# NodeMCU-Gateway.net
KiCad netlist of a schematic drawn in EAGLE
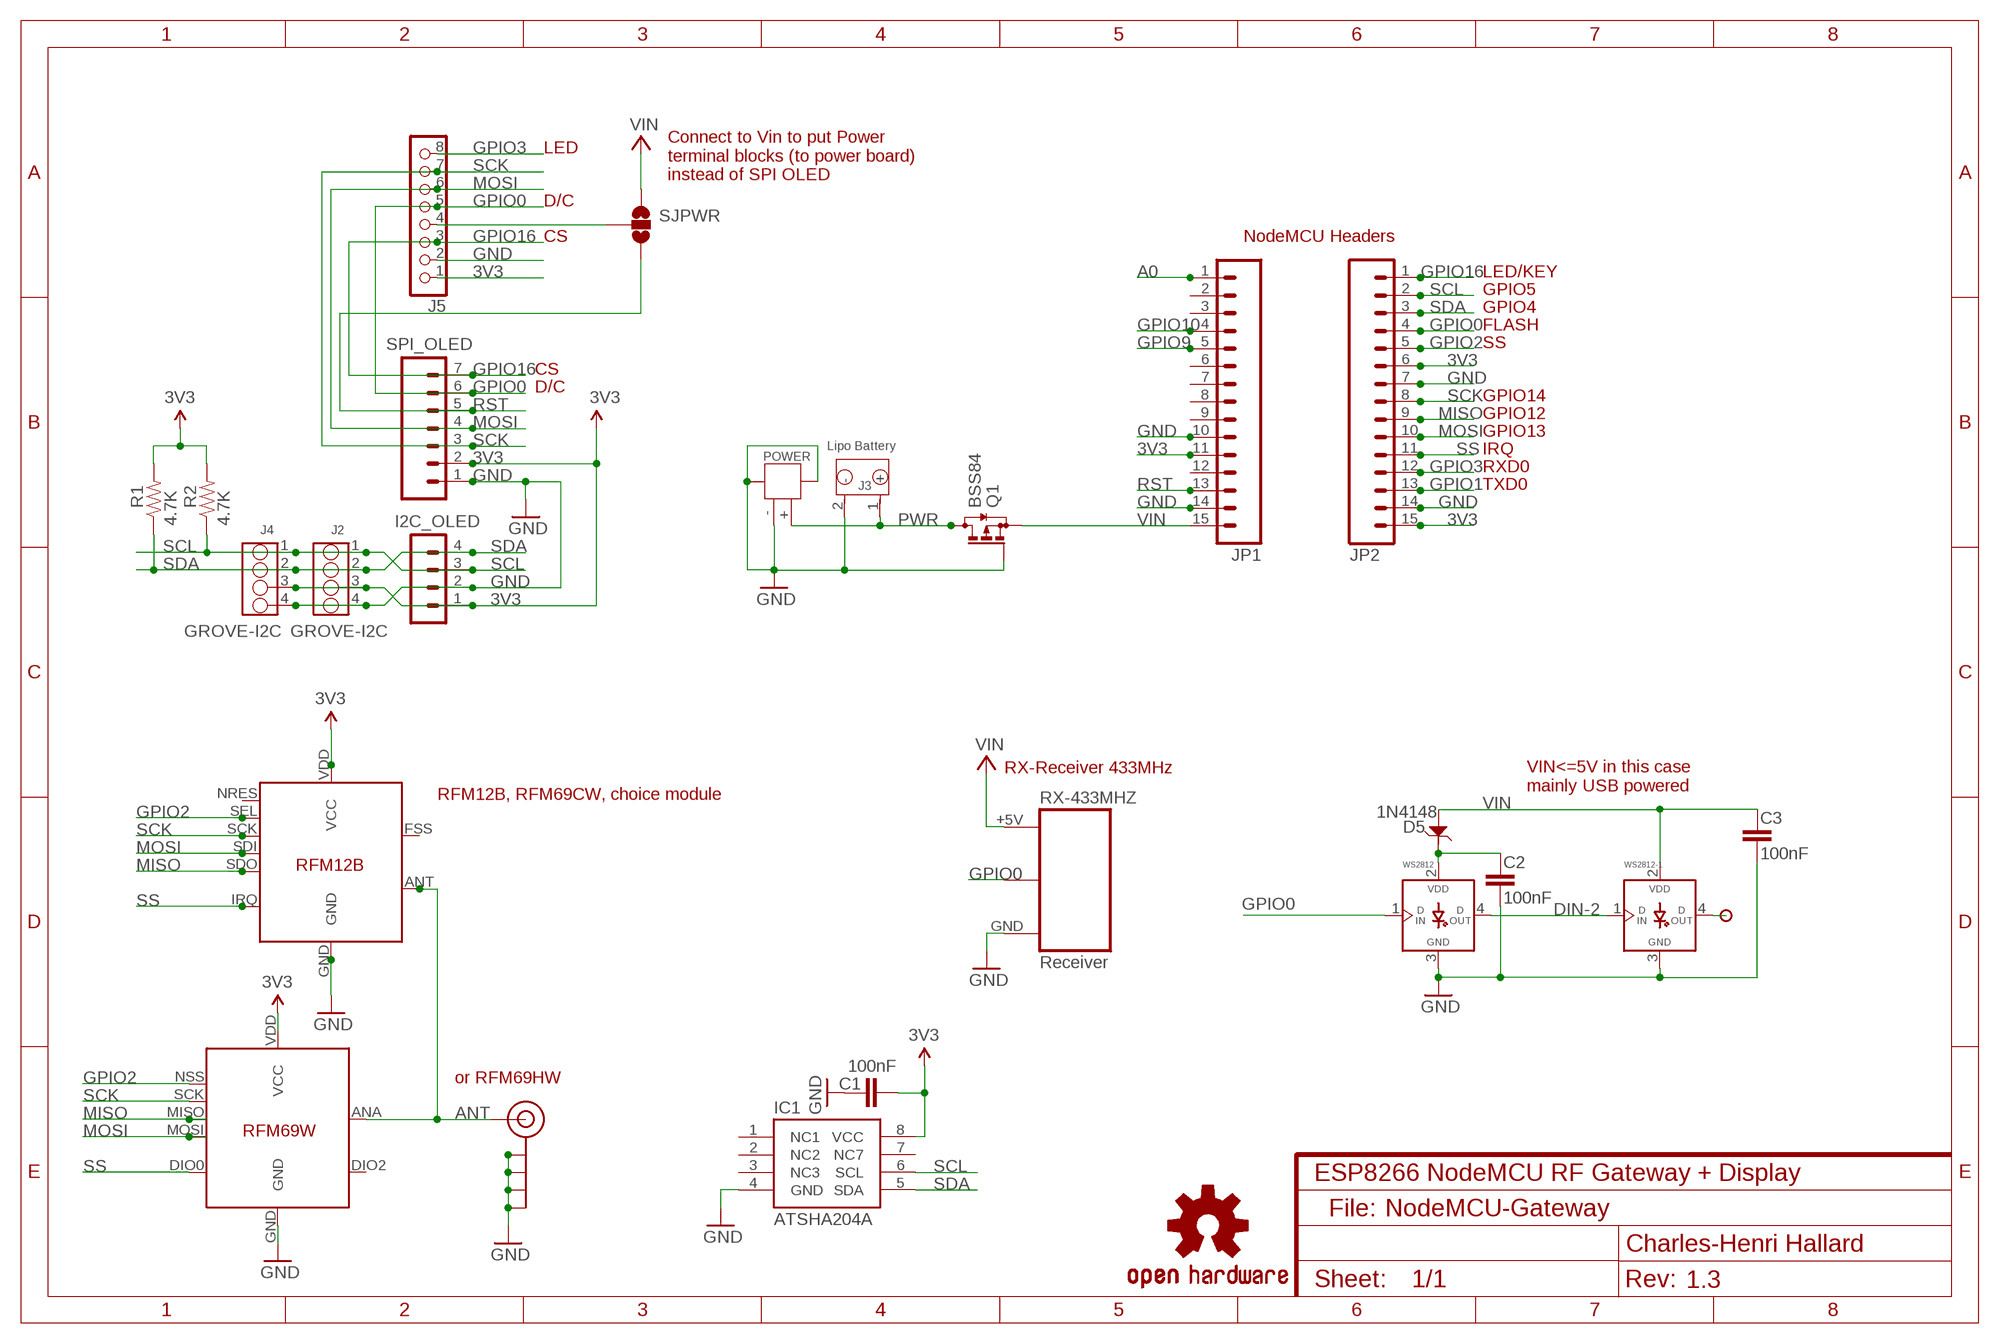
[diagram p0: schematic, sheet 1]

(export (version "E")
  (design (tool "Eeschema 10.0.6"))
  (components
    (comp (ref "C1")
      (value "100nF")
      (footprint "eagle-import:0805-CAP")
      (libsource (lib "eagle-import") (part "CAP0805-CAP"))
    )
    (comp (ref "C2")
      (value "100nF")
      (footprint "eagle-import:0805-CAP")
      (libsource (lib "eagle-import") (part "CAP0805-CAP"))
    )
    (comp (ref "C3")
      (value "100nF")
      (footprint "eagle-import:0805-CAP")
      (libsource (lib "eagle-import") (part "CAP0805-CAP"))
    )
    (comp (ref "D5")
      (value "1N4148")
      (footprint "eagle-import:SOD123-2.7X1.6")
      (libsource (lib "eagle-import") (part "D-ESD-2P-CESD5V0D1"))
    )
    (comp (ref "I2C_OLED")
      (value "CON_HEADER_1X04'LOCK'")
      (footprint "eagle-import:1X04_LOCK")
      (libsource (lib "eagle-import") (part "CON_HEADER_1X04'LOCK'"))
    )
    (comp (ref "IC1")
      (value "ATSHA204A")
      (footprint "eagle-import:SOIC8")
      (libsource (lib "eagle-import") (part "ATSHA204_SOIC8"))
    )
    (comp (ref "J$2")
      (value "ANTENNATINY")
      (footprint "eagle-import:SMA_UFL_PAD_TINY")
      (libsource (lib "eagle-import") (part "ANTENNATINY"))
    )
    (comp (ref "J2")
      (value "GROVE-I2C")
      (footprint "eagle-import:4P-2.0-90D")
      (libsource (lib "eagle-import") (part "GROVE-4P-2.0-3470140P1"))
    )
    (comp (ref "J3")
      (value "Lipo Battery")
      (footprint "eagle-import:2P-2.0-90D")
      (libsource (lib "eagle-import") (part "JST-2P-PW-3410070P1"))
    )
    (comp (ref "J4")
      (value "GROVE-I2C")
      (footprint "eagle-import:4P-2.0")
      (libsource (lib "eagle-import") (part "GROVE-4P-2.0-3470130P1"))
    )
    (comp (ref "J5")
      (value "CON_HEADER_1X08-PTH")
      (footprint "eagle-import:M1X8")
      (libsource (lib "eagle-import") (part "CON_HEADER_1X08-PTH"))
    )
    (comp (ref "JP1")
      (value "M15LOCK")
      (footprint "eagle-import:1X15_LOCK")
      (libsource (lib "eagle-import") (part "M15LOCK"))
    )
    (comp (ref "JP2")
      (value "M15LOCK")
      (footprint "eagle-import:1X15_LOCK")
      (libsource (lib "eagle-import") (part "M15LOCK"))
    )
    (comp (ref "LOGO2")
      (value "OSHW-LOGOL")
      (footprint "eagle-import:OSHW-LOGO-L")
      (libsource (lib "eagle-import") (part "OSHW-LOGOL"))
    )
    (comp (ref "P2")
      (value "PADNORMAL")
      (footprint "eagle-import:PAD")
      (libsource (lib "eagle-import") (part "PADNORMAL"))
    )
    (comp (ref "POWER")
      (value "JST-2P-SMD'2.0'")
      (footprint "eagle-import:2P-SMD-2.0-90D")
      (libsource (lib "eagle-import") (part "JST-2P-SMD'2.0'"))
    )
    (comp (ref "Q1")
      (value "BSS84")
      (footprint "eagle-import:SOT23")
      (libsource (lib "eagle-import") (part "BSS84"))
    )
    (comp (ref "R1")
      (value "4.7K")
      (footprint "eagle-import:0805-RES")
      (libsource (lib "eagle-import") (part "RESISTOR0805-RES"))
    )
    (comp (ref "R2")
      (value "4.7K")
      (footprint "eagle-import:0805-RES")
      (libsource (lib "eagle-import") (part "RESISTOR0805-RES"))
    )
    (comp (ref "RX-433MHZ")
      (value "Receiver")
      (footprint "eagle-import:RF-LINK_RX_NO_SILK")
      (libsource (lib "eagle-import") (part "RF-LINK_RX"))
    )
    (comp (ref "SJPWR")
      (value "JUMPER-PAD-3-2OF3_NC_BY_TRACE_LARGE")
      (footprint "eagle-import:PAD-JUMPER-3-2OF3_NC_BY_TRACE_YES_SILK_LARGE")
      (libsource (lib "eagle-import") (part "JUMPER-PAD-3-2OF3_NC_BY_TRACE_LARGE"))
    )
    (comp (ref "SPI_OLED")
      (value "CON_HEADER_1X07'SMALL'")
      (footprint "eagle-import:M1X7")
      (libsource (lib "eagle-import") (part "CON_HEADER_1X07'SMALL'"))
    )
    (comp (ref "U$2")
      (value "RFM12B")
      (footprint "eagle-import:RFM12B-MINPADS")
      (libsource (lib "eagle-import") (part "RFM12B"))
    )
    (comp (ref "U$3")
      (value "RFM69W")
      (footprint "eagle-import:RFM69W-MINPADS")
      (libsource (lib "eagle-import") (part "RFM69W"))
    )
    (comp (ref "WS2812")
      (value "WS2812B")
      (footprint "eagle-import:WS2812-PTH")
      (libsource (lib "eagle-import") (part "WS2812B5MM"))
    )
    (comp (ref "WS2812-1")
      (value "WS2812B")
      (footprint "eagle-import:WS2812-PTH")
      (libsource (lib "eagle-import") (part "WS2812B5MM"))
    )
  )
  (nets
    (net (code "1") (name "/A0") (class "Default")
      (node (ref "JP1") (pin "1") (pinfunction "1_1") (pintype "passive"))
    )
    (net (code "2") (name "/ANT") (class "Default")
      (node (ref "J$2") (pin "ANT1") (pinfunction "SIGNAL_ANT1") (pintype "bidirectional"))
      (node (ref "J$2") (pin "ANT2") (pinfunction "SIGNAL_ANT2") (pintype "bidirectional"))
      (node (ref "J$2") (pin "ANT3") (pinfunction "SIGNAL_ANT3") (pintype "bidirectional"))
      (node (ref "U$2") (pin "ANT") (pinfunction "ANT_ANT") (pintype "passive"))
      (node (ref "U$3") (pin "ANA") (pinfunction "ANT_ANA") (pintype "passive"))
    )
    (net (code "3") (name "/DIN-2") (class "Default")
      (node (ref "WS2812") (pin "4") (pinfunction "DOUT_4") (pintype "output"))
      (node (ref "WS2812-1") (pin "1") (pinfunction "DIN_1") (pintype "input"))
    )
    (net (code "4") (name "/GPIO0") (class "Default")
      (node (ref "J5") (pin "5") (pinfunction "5_5") (pintype "passive"))
      (node (ref "JP2") (pin "4") (pinfunction "4_4") (pintype "passive"))
      (node (ref "RX-433MHZ") (pin "DATA@1") (pinfunction "DATA_DATA@1") (pintype "output"))
      (node (ref "RX-433MHZ") (pin "DATA@2") (pinfunction "DATA_DATA@2") (pintype "output"))
      (node (ref "SPI_OLED") (pin "6") (pinfunction "6_6") (pintype "passive"))
      (node (ref "WS2812") (pin "1") (pinfunction "DIN_1") (pintype "input"))
    )
    (net (code "5") (name "/GPIO1") (class "Default")
      (node (ref "JP2") (pin "13") (pinfunction "13_13") (pintype "passive"))
    )
    (net (code "6") (name "/GPIO2") (class "Default")
      (node (ref "JP2") (pin "5") (pinfunction "5_5") (pintype "passive"))
      (node (ref "U$2") (pin "SEL") (pinfunction "SEL_SEL") (pintype "input"))
      (node (ref "U$3") (pin "NSS") (pinfunction "SEL_NSS") (pintype "input"))
    )
    (net (code "7") (name "/GPIO3") (class "Default")
      (node (ref "J5") (pin "8") (pinfunction "8_8") (pintype "passive"))
      (node (ref "JP2") (pin "12") (pinfunction "12_12") (pintype "passive"))
    )
    (net (code "8") (name "/GPIO9") (class "Default")
      (node (ref "JP1") (pin "5") (pinfunction "5_5") (pintype "passive"))
    )
    (net (code "9") (name "/GPIO10") (class "Default")
      (node (ref "JP1") (pin "4") (pinfunction "4_4") (pintype "passive"))
    )
    (net (code "10") (name "/GPIO16") (class "Default")
      (node (ref "J5") (pin "3") (pinfunction "3_3") (pintype "passive"))
      (node (ref "JP2") (pin "1") (pinfunction "1_1") (pintype "passive"))
      (node (ref "SPI_OLED") (pin "7") (pinfunction "7_7") (pintype "passive"))
    )
    (net (code "11") (name "/MISO") (class "Default")
      (node (ref "JP2") (pin "9") (pinfunction "9_9") (pintype "passive"))
      (node (ref "U$2") (pin "SDO") (pinfunction "SDO_SDO") (pintype "output"))
      (node (ref "U$3") (pin "MISO") (pinfunction "MISO_MISO") (pintype "input"))
    )
    (net (code "12") (name "/MOSI") (class "Default")
      (node (ref "J5") (pin "6") (pinfunction "6_6") (pintype "passive"))
      (node (ref "JP2") (pin "10") (pinfunction "10_10") (pintype "passive"))
      (node (ref "SPI_OLED") (pin "4") (pinfunction "4_4") (pintype "passive"))
      (node (ref "U$2") (pin "SDI") (pinfunction "SDI_SDI") (pintype "input"))
      (node (ref "U$3") (pin "MOSI") (pinfunction "MOSI_MOSI") (pintype "output"))
    )
    (net (code "13") (name "/PWR") (class "Default")
      (node (ref "J3") (pin "1") (pinfunction "+_1") (pintype "bidirectional"))
      (node (ref "POWER") (pin "+") (pinfunction "1_+") (pintype "bidirectional"))
      (node (ref "Q1") (pin "3") (pinfunction "D_3") (pintype "passive"))
    )
    (net (code "14") (name "/RST") (class "Default")
      (node (ref "JP1") (pin "13") (pinfunction "13_13") (pintype "passive"))
      (node (ref "SJPWR") (pin "3") (pinfunction "3_3") (pintype "passive"))
      (node (ref "SPI_OLED") (pin "5") (pinfunction "5_5") (pintype "passive"))
    )
    (net (code "15") (name "/SCK") (class "Default")
      (node (ref "J5") (pin "7") (pinfunction "7_7") (pintype "passive"))
      (node (ref "JP2") (pin "8") (pinfunction "8_8") (pintype "passive"))
      (node (ref "SPI_OLED") (pin "3") (pinfunction "3_3") (pintype "passive"))
      (node (ref "U$2") (pin "SCK") (pinfunction "SCK_SCK") (pintype "input"))
      (node (ref "U$3") (pin "SCK") (pinfunction "SCK_SCK") (pintype "input"))
    )
    (net (code "16") (name "/SCL") (class "Default")
      (node (ref "I2C_OLED") (pin "3") (pinfunction "3_3") (pintype "passive"))
      (node (ref "IC1") (pin "6") (pinfunction "SCL_6") (pintype "bidirectional"))
      (node (ref "J2") (pin "1") (pinfunction "1_1") (pintype "bidirectional"))
      (node (ref "J4") (pin "1") (pinfunction "1_1") (pintype "bidirectional"))
      (node (ref "JP2") (pin "2") (pinfunction "2_2") (pintype "passive"))
      (node (ref "R2") (pin "1") (pinfunction "1_1") (pintype "passive"))
    )
    (net (code "17") (name "/SDA") (class "Default")
      (node (ref "I2C_OLED") (pin "4") (pinfunction "4_4") (pintype "passive"))
      (node (ref "IC1") (pin "5") (pinfunction "SDA_5") (pintype "bidirectional"))
      (node (ref "J2") (pin "2") (pinfunction "2_2") (pintype "bidirectional"))
      (node (ref "J4") (pin "2") (pinfunction "2_2") (pintype "bidirectional"))
      (node (ref "JP2") (pin "3") (pinfunction "3_3") (pintype "passive"))
      (node (ref "R1") (pin "1") (pinfunction "1_1") (pintype "passive"))
    )
    (net (code "18") (name "/SS") (class "Default")
      (node (ref "JP2") (pin "11") (pinfunction "11_11") (pintype "passive"))
      (node (ref "U$2") (pin "IRQ") (pinfunction "IRQ_IRQ") (pintype "open_collector"))
      (node (ref "U$3") (pin "DIO0") (pinfunction "DIO0_DIO0") (pintype "open_collector"))
    )
    (net (code "19") (name "3V3") (class "Default")
      (node (ref "C1") (pin "2") (pinfunction "2_2") (pintype "passive"))
      (node (ref "I2C_OLED") (pin "1") (pinfunction "1_1") (pintype "passive"))
      (node (ref "IC1") (pin "8") (pinfunction "VCC_8") (pintype "power_in"))
      (node (ref "J2") (pin "3") (pinfunction "3_3") (pintype "bidirectional"))
      (node (ref "J4") (pin "3") (pinfunction "3_3") (pintype "bidirectional"))
      (node (ref "J5") (pin "1") (pinfunction "1_1") (pintype "passive"))
      (node (ref "JP1") (pin "11") (pinfunction "11_11") (pintype "passive"))
      (node (ref "JP2") (pin "15") (pinfunction "15_15") (pintype "passive"))
      (node (ref "JP2") (pin "6") (pinfunction "6_6") (pintype "passive"))
      (node (ref "R1") (pin "2") (pinfunction "2_2") (pintype "passive"))
      (node (ref "R2") (pin "2") (pinfunction "2_2") (pintype "passive"))
      (node (ref "SPI_OLED") (pin "2") (pinfunction "2_2") (pintype "passive"))
      (node (ref "U$2") (pin "VDD") (pinfunction "VCC_VDD") (pintype "power_in"))
      (node (ref "U$3") (pin "VDD") (pinfunction "VCC_VDD") (pintype "power_in"))
    )
    (net (code "20") (name "GND") (class "Default")
      (node (ref "C1") (pin "1") (pinfunction "1_1") (pintype "passive"))
      (node (ref "C2") (pin "1") (pinfunction "1_1") (pintype "passive"))
      (node (ref "C3") (pin "1") (pinfunction "1_1") (pintype "passive"))
      (node (ref "I2C_OLED") (pin "2") (pinfunction "2_2") (pintype "passive"))
      (node (ref "IC1") (pin "4") (pinfunction "GND_4") (pintype "power_in"))
      (node (ref "J$2") (pin "GND1") (pinfunction "GND_GND1") (pintype "bidirectional"))
      (node (ref "J$2") (pin "GND2") (pinfunction "GND_GND2") (pintype "bidirectional"))
      (node (ref "J$2") (pin "GND3") (pinfunction "GND_GND3") (pintype "bidirectional"))
      (node (ref "J$2") (pin "GND4") (pinfunction "GND_GND4") (pintype "bidirectional"))
      (node (ref "J2") (pin "4") (pinfunction "4_4") (pintype "bidirectional"))
      (node (ref "J3") (pin "2") (pinfunction "-_2") (pintype "bidirectional"))
      (node (ref "J4") (pin "4") (pinfunction "4_4") (pintype "bidirectional"))
      (node (ref "J5") (pin "2") (pinfunction "2_2") (pintype "passive"))
      (node (ref "JP1") (pin "10") (pinfunction "10_10") (pintype "passive"))
      (node (ref "JP1") (pin "14") (pinfunction "14_14") (pintype "passive"))
      (node (ref "JP2") (pin "14") (pinfunction "14_14") (pintype "passive"))
      (node (ref "JP2") (pin "7") (pinfunction "7_7") (pintype "passive"))
      (node (ref "POWER") (pin "-") (pinfunction "2_-") (pintype "bidirectional"))
      (node (ref "POWER") (pin "3") (pinfunction "3_3") (pintype "bidirectional"))
      (node (ref "POWER") (pin "4") (pinfunction "4_4") (pintype "bidirectional"))
      (node (ref "Q1") (pin "1") (pinfunction "G_1") (pintype "passive"))
      (node (ref "RX-433MHZ") (pin "GND") (pinfunction "GND_GND") (pintype "power_in"))
      (node (ref "SPI_OLED") (pin "1") (pinfunction "1_1") (pintype "passive"))
      (node (ref "U$2") (pin "GND") (pinfunction "GND_GND") (pintype "power_in"))
      (node (ref "U$3") (pin "GND") (pinfunction "GND_GND") (pintype "power_in"))
      (node (ref "WS2812") (pin "3") (pinfunction "GND_3") (pintype "power_in"))
      (node (ref "WS2812-1") (pin "3") (pinfunction "GND_3") (pintype "power_in"))
    )
    (net (code "21") (name "Net-(J5-Pad4)") (class "Default")
      (node (ref "J5") (pin "4") (pinfunction "4_4") (pintype "passive"))
      (node (ref "SJPWR") (pin "2") (pinfunction "2_2") (pintype "passive"))
    )
    (net (code "22") (name "Net-(WS2812-1-DOUT)") (class "Default")
      (node (ref "P2") (pin "1") (pinfunction "1_1") (pintype "bidirectional"))
      (node (ref "WS2812-1") (pin "4") (pinfunction "DOUT_4") (pintype "output"))
    )
    (net (code "23") (name "Net-(WS2812-VDD)") (class "Default")
      (node (ref "C2") (pin "2") (pinfunction "2_2") (pintype "passive"))
      (node (ref "D5") (pin "2") (pinfunction "2_2") (pintype "bidirectional"))
      (node (ref "WS2812") (pin "2") (pinfunction "VDD_2") (pintype "power_in"))
    )
    (net (code "24") (name "VIN") (class "Default")
      (node (ref "C3") (pin "2") (pinfunction "2_2") (pintype "passive"))
      (node (ref "D5") (pin "1") (pinfunction "1_1") (pintype "bidirectional"))
      (node (ref "JP1") (pin "15") (pinfunction "15_15") (pintype "passive"))
      (node (ref "Q1") (pin "2") (pinfunction "S_2") (pintype "passive"))
      (node (ref "RX-433MHZ") (pin "+5V") (pinfunction "+5V_+5V") (pintype "power_in"))
      (node (ref "SJPWR") (pin "1") (pinfunction "1_1") (pintype "passive"))
      (node (ref "WS2812-1") (pin "2") (pinfunction "VDD_2") (pintype "power_in"))
    )
    (net (code "25") (name "unconnected-(IC1-NC1-Pad1)") (class "Default")
      (node (ref "IC1") (pin "1") (pinfunction "NC1_1") (pintype "no_connect"))
    )
    (net (code "26") (name "unconnected-(IC1-NC2-Pad2)") (class "Default")
      (node (ref "IC1") (pin "2") (pinfunction "NC2_2") (pintype "no_connect"))
    )
    (net (code "27") (name "unconnected-(IC1-NC3-Pad3)") (class "Default")
      (node (ref "IC1") (pin "3") (pinfunction "NC3_3") (pintype "no_connect"))
    )
    (net (code "28") (name "unconnected-(IC1-NC7-Pad7)") (class "Default")
      (node (ref "IC1") (pin "7") (pinfunction "NC7_7") (pintype "no_connect"))
    )
    (net (code "29") (name "unconnected-(JP1-Pad2)") (class "Default")
      (node (ref "JP1") (pin "2") (pinfunction "2_2") (pintype "passive"))
    )
    (net (code "30") (name "unconnected-(JP1-Pad3)") (class "Default")
      (node (ref "JP1") (pin "3") (pinfunction "3_3") (pintype "passive"))
    )
    (net (code "31") (name "unconnected-(JP1-Pad6)") (class "Default")
      (node (ref "JP1") (pin "6") (pinfunction "6_6") (pintype "passive"))
    )
    (net (code "32") (name "unconnected-(JP1-Pad7)") (class "Default")
      (node (ref "JP1") (pin "7") (pinfunction "7_7") (pintype "passive"))
    )
    (net (code "33") (name "unconnected-(JP1-Pad8)") (class "Default")
      (node (ref "JP1") (pin "8") (pinfunction "8_8") (pintype "passive"))
    )
    (net (code "34") (name "unconnected-(JP1-Pad9)") (class "Default")
      (node (ref "JP1") (pin "9") (pinfunction "9_9") (pintype "passive"))
    )
    (net (code "35") (name "unconnected-(JP1-Pad12)") (class "Default")
      (node (ref "JP1") (pin "12") (pinfunction "12_12") (pintype "passive"))
    )
    (net (code "36") (name "unconnected-(U$2-FFS-PadFSS)") (class "Default")
      (node (ref "U$2") (pin "FSS") (pinfunction "FFS_FSS") (pintype "bidirectional"))
    )
    (net (code "37") (name "unconnected-(U$2-PadNRES)") (class "Default")
      (node (ref "U$2") (pin "NRES") (pinfunction "NRES_NRES") (pintype "input"))
    )
    (net (code "38") (name "unconnected-(U$3-PadDIO2)") (class "Default")
      (node (ref "U$3") (pin "DIO2") (pinfunction "DIO2_DIO2") (pintype "open_collector"))
    )
  )
)
